# DragonHeadv2.net
KiCad netlist of a schematic drawn in EAGLE
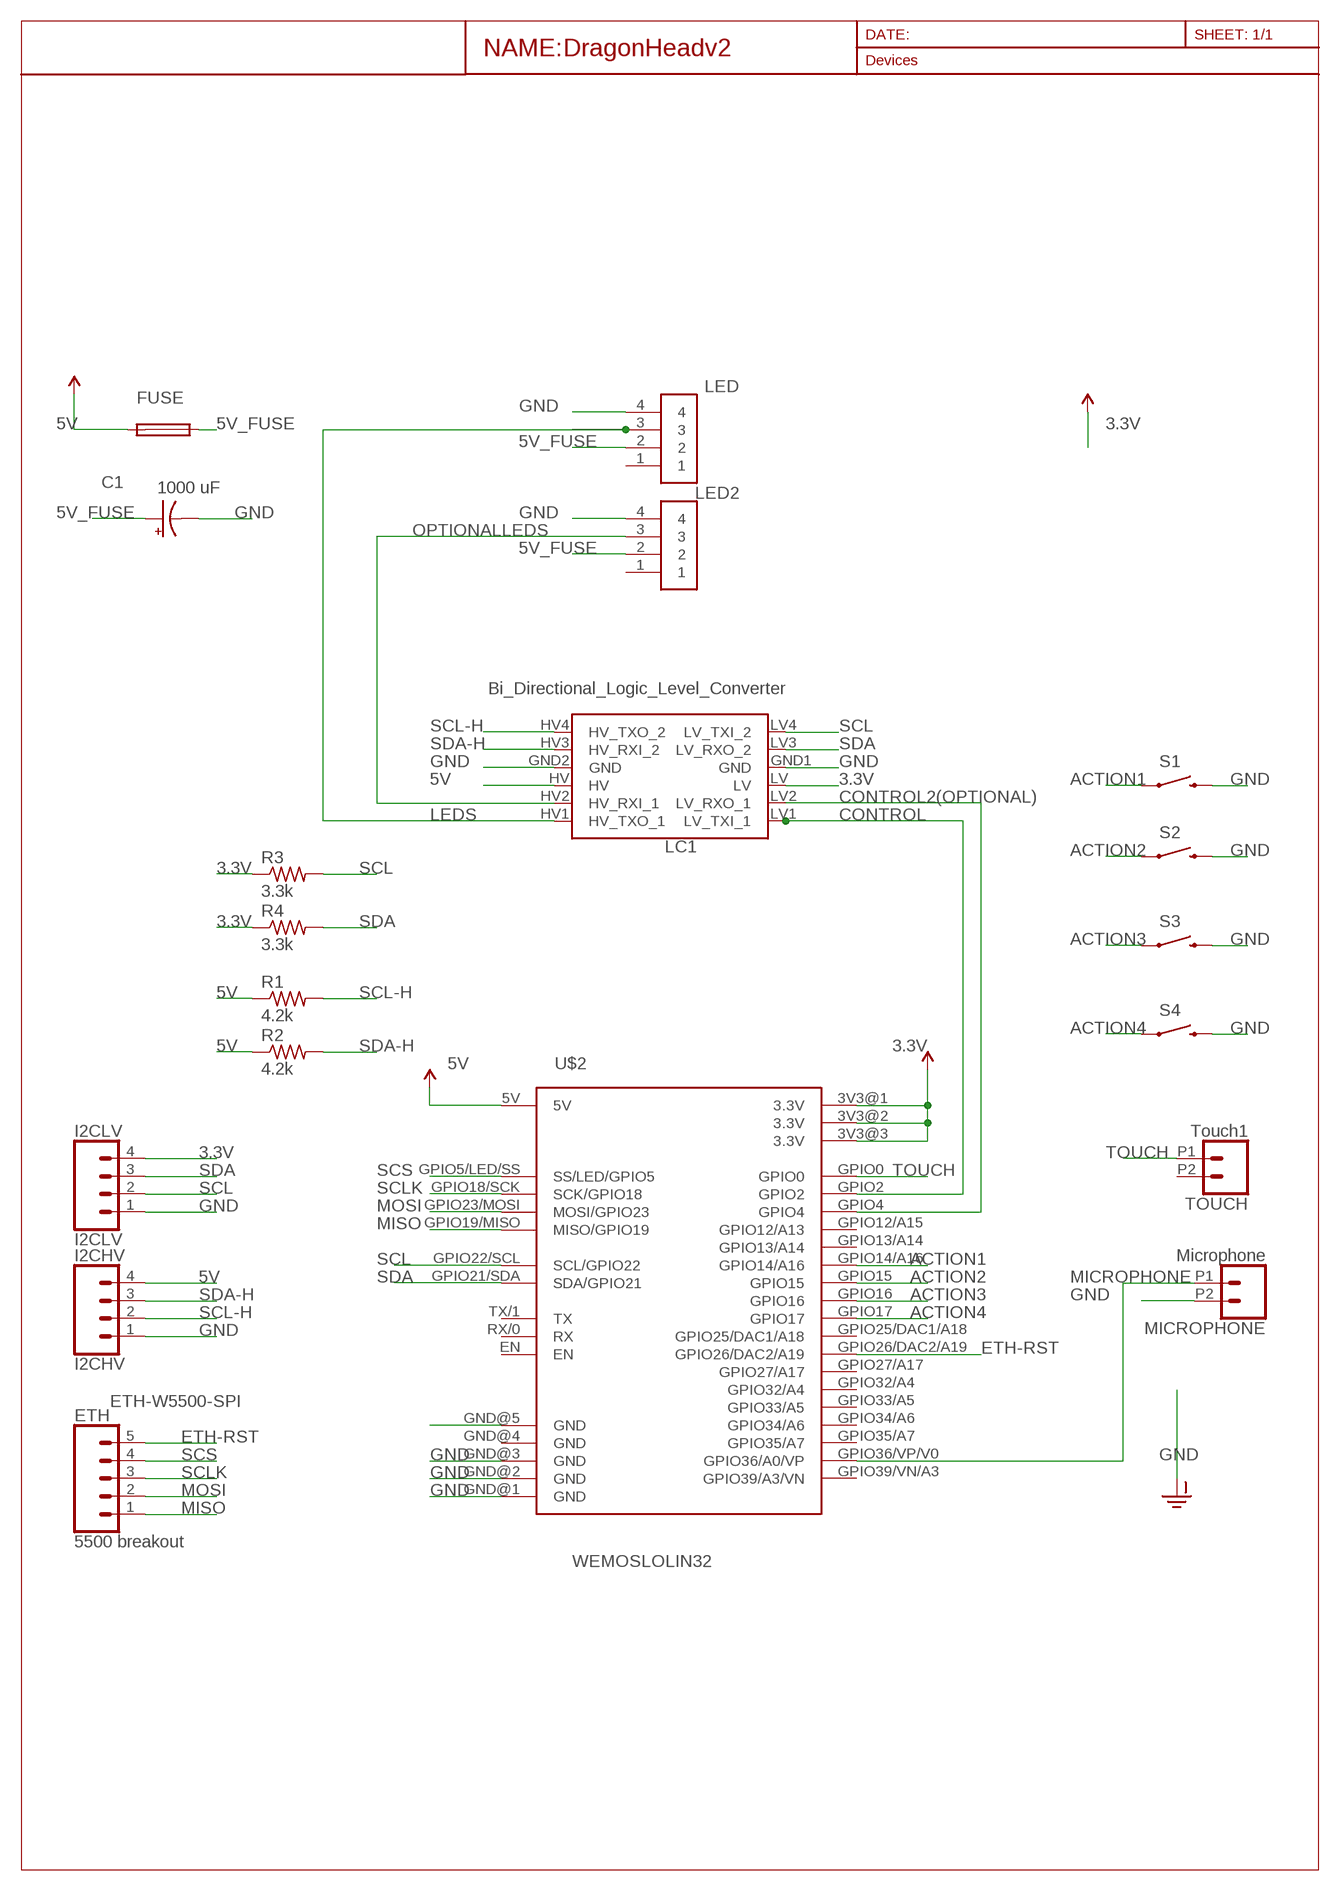
[diagram p0: schematic, sheet 1]

(export (version "E")
  (design (tool "Eeschema 10.0.6"))
  (components
    (comp (ref "C1")
      (value "1000 uF")
      (footprint "eagle-import:CPOL-RADIAL-5MM-10MM")
      (libsource (lib "eagle-import") (part "1000UF-RADIAL-5MM-25V-20%"))
    )
    (comp (ref "ETH")
      (value "5500 breakout")
      (footprint "eagle-import:1X05")
      (libsource (lib "eagle-import") (part "CONN_05"))
    )
    (comp (ref "FUSE")
      (value "FUSEBLANK_5X20MM")
      (footprint "eagle-import:FUSE_HOLDER_5X20MM")
      (libsource (lib "eagle-import") (part "FUSEBLANK_5X20MM"))
    )
    (comp (ref "I2CHV")
      (value "I2CHV")
      (footprint "eagle-import:1X04")
      (libsource (lib "eagle-import") (part "CONN_04PTH"))
    )
    (comp (ref "I2CLV")
      (value "I2CLV")
      (footprint "eagle-import:1X04")
      (libsource (lib "eagle-import") (part "CONN_04PTH"))
    )
    (comp (ref "LC1")
      (value "Bi_Directional_Logic_Level_Converter")
      (footprint "eagle-import:SPARKFUN_LOGIC_LEVEL_CONVERTER")
      (libsource (lib "eagle-import") (part "SPARKFUN_LOGIC_LEVEL_CONVERTER"))
    )
    (comp (ref "LED")
      (value "231-334/001-000")
      (footprint "eagle-import:WAGO_231-334_001-000")
      (fields (field (name "MF") "WAGO"))
      (libsource (lib "eagle-import") (part "231-334/001-000"))
    )
    (comp (ref "LED2")
      (value "231-334/001-000")
      (footprint "eagle-import:WAGO_231-334_001-000")
      (fields (field (name "MF") "WAGO"))
      (libsource (lib "eagle-import") (part "231-334/001-000"))
    )
    (comp (ref "MICROPHONE")
      (value "Microphone")
      (footprint "eagle-import:1X02_2.54_SCREWTERM")
      (libsource (lib "eagle-import") (part "CONN_022.54MM_SCREWTERM"))
    )
    (comp (ref "R1")
      (value "4.2k")
      (footprint "eagle-import:0204_7")
      (libsource (lib "eagle-import") (part "R-US_0204/7"))
    )
    (comp (ref "R2")
      (value "4.2k")
      (footprint "eagle-import:0204_7")
      (libsource (lib "eagle-import") (part "R-US_0204/7"))
    )
    (comp (ref "R3")
      (value "3.3k")
      (footprint "eagle-import:0204_7")
      (libsource (lib "eagle-import") (part "R-US_0204/7"))
    )
    (comp (ref "R4")
      (value "3.3k")
      (footprint "eagle-import:0204_7")
      (libsource (lib "eagle-import") (part "R-US_0204/7"))
    )
    (comp (ref "S1")
      (value "SWITCH-MOMENTARY-2SIDE_EZ")
      (footprint "eagle-import:TACTILE-PTH-SIDEEZ")
      (libsource (lib "eagle-import") (part "SWITCH-MOMENTARY-2SIDE_EZ"))
    )
    (comp (ref "S2")
      (value "SWITCH-MOMENTARY-2SIDE_EZ")
      (footprint "eagle-import:TACTILE-PTH-SIDEEZ")
      (libsource (lib "eagle-import") (part "SWITCH-MOMENTARY-2SIDE_EZ"))
    )
    (comp (ref "S3")
      (value "SWITCH-MOMENTARY-2SIDE_EZ")
      (footprint "eagle-import:TACTILE-PTH-SIDEEZ")
      (libsource (lib "eagle-import") (part "SWITCH-MOMENTARY-2SIDE_EZ"))
    )
    (comp (ref "S4")
      (value "SWITCH-MOMENTARY-2SIDE_EZ")
      (footprint "eagle-import:TACTILE-PTH-SIDEEZ")
      (libsource (lib "eagle-import") (part "SWITCH-MOMENTARY-2SIDE_EZ"))
    )
    (comp (ref "TOUCH")
      (value "Touch1")
      (footprint "eagle-import:1X02_2.54_SCREWTERM")
      (libsource (lib "eagle-import") (part "CONN_022.54MM_SCREWTERM"))
    )
    (comp (ref "U$2")
      (value "WEMOSLOLIN32")
      (footprint "eagle-import:LOLIN32VAR1")
      (libsource (lib "eagle-import") (part "WEMOSLOLIN32"))
    )
  )
  (nets
    (net (code "1") (name "/5V_FUSE") (class "Default")
      (node (ref "C1") (pin "+") (pinfunction "+_+") (pintype "passive"))
      (node (ref "FUSE") (pin "1") (pinfunction "1_1") (pintype "passive"))
      (node (ref "LED") (pin "2") (pinfunction "2_2") (pintype "passive"))
      (node (ref "LED2") (pin "2") (pinfunction "2_2") (pintype "passive"))
    )
    (net (code "2") (name "/ACTION1") (class "Default")
      (node (ref "S1") (pin "1") (pinfunction "1_1") (pintype "passive"))
      (node (ref "U$2") (pin "GPIO14/A16") (pinfunction "GPIO14/A16_GPIO14/A16") (pintype "bidirectional"))
    )
    (net (code "3") (name "/ACTION2") (class "Default")
      (node (ref "S2") (pin "1") (pinfunction "1_1") (pintype "passive"))
      (node (ref "U$2") (pin "GPIO15") (pinfunction "GPIO15_GPIO15") (pintype "bidirectional"))
    )
    (net (code "4") (name "/ACTION3") (class "Default")
      (node (ref "S3") (pin "1") (pinfunction "1_1") (pintype "passive"))
      (node (ref "U$2") (pin "GPIO16") (pinfunction "GPIO16_GPIO16") (pintype "bidirectional"))
    )
    (net (code "5") (name "/ACTION4") (class "Default")
      (node (ref "S4") (pin "1") (pinfunction "1_1") (pintype "passive"))
      (node (ref "U$2") (pin "GPIO17") (pinfunction "GPIO17_GPIO17") (pintype "bidirectional"))
    )
    (net (code "6") (name "/CONTROL") (class "Default")
      (node (ref "LC1") (pin "LV1") (pinfunction "LV_TXI_1_LV1") (pintype "bidirectional"))
      (node (ref "U$2") (pin "GPIO2") (pinfunction "GPIO2_GPIO2") (pintype "bidirectional"))
    )
    (net (code "7") (name "/CONTROL2(OPTIONAL)") (class "Default")
      (node (ref "LC1") (pin "LV2") (pinfunction "LV_RXO_1_LV2") (pintype "bidirectional"))
      (node (ref "U$2") (pin "GPIO4") (pinfunction "GPIO4_GPIO4") (pintype "bidirectional"))
    )
    (net (code "8") (name "/ETH-RST") (class "Default")
      (node (ref "ETH") (pin "5") (pinfunction "5_5") (pintype "passive"))
      (node (ref "U$2") (pin "GPIO26/DAC2/A19") (pinfunction "GPIO26/DAC2/A19_GPIO26/DAC2/A19") (pintype "bidirectional"))
    )
    (net (code "9") (name "/LEDS") (class "Default")
      (node (ref "LC1") (pin "HV1") (pinfunction "HV_TXO_1_HV1") (pintype "bidirectional"))
      (node (ref "LED") (pin "3") (pinfunction "3_3") (pintype "passive"))
    )
    (net (code "10") (name "/MICROPHONE") (class "Default")
      (node (ref "MICROPHONE") (pin "P1") (pinfunction "1_P1") (pintype "passive"))
      (node (ref "U$2") (pin "GPIO36/VP/V0") (pinfunction "GPIO36/A0/VP_GPIO36/VP/V0") (pintype "bidirectional"))
    )
    (net (code "11") (name "/MISO") (class "Default")
      (node (ref "ETH") (pin "1") (pinfunction "1_1") (pintype "passive"))
      (node (ref "U$2") (pin "GPIO19/MISO") (pinfunction "MISO/GPIO19_GPIO19/MISO") (pintype "bidirectional"))
    )
    (net (code "12") (name "/MOSI") (class "Default")
      (node (ref "ETH") (pin "2") (pinfunction "2_2") (pintype "passive"))
      (node (ref "U$2") (pin "GPIO23/MOSI") (pinfunction "MOSI/GPIO23_GPIO23/MOSI") (pintype "bidirectional"))
    )
    (net (code "13") (name "/OPTIONALLEDS") (class "Default")
      (node (ref "LC1") (pin "HV2") (pinfunction "HV_RXI_1_HV2") (pintype "bidirectional"))
      (node (ref "LED2") (pin "3") (pinfunction "3_3") (pintype "passive"))
    )
    (net (code "14") (name "/SCL") (class "Default")
      (node (ref "I2CLV") (pin "2") (pinfunction "2_2") (pintype "passive"))
      (node (ref "LC1") (pin "LV4") (pinfunction "LV_TXI_2_LV4") (pintype "bidirectional"))
      (node (ref "R3") (pin "2") (pinfunction "2_2") (pintype "passive"))
      (node (ref "U$2") (pin "GPIO22/SCL") (pinfunction "SCL/GPIO22_GPIO22/SCL") (pintype "bidirectional"))
    )
    (net (code "15") (name "/SCL-H") (class "Default")
      (node (ref "I2CHV") (pin "2") (pinfunction "2_2") (pintype "passive"))
      (node (ref "LC1") (pin "HV4") (pinfunction "HV_TXO_2_HV4") (pintype "bidirectional"))
      (node (ref "R1") (pin "2") (pinfunction "2_2") (pintype "passive"))
    )
    (net (code "16") (name "/SCLK") (class "Default")
      (node (ref "ETH") (pin "3") (pinfunction "3_3") (pintype "passive"))
      (node (ref "U$2") (pin "GPIO18/SCK") (pinfunction "SCK/GPIO18_GPIO18/SCK") (pintype "bidirectional"))
    )
    (net (code "17") (name "/SCS") (class "Default")
      (node (ref "ETH") (pin "4") (pinfunction "4_4") (pintype "passive"))
      (node (ref "U$2") (pin "GPIO5/LED/SS") (pinfunction "SS/LED/GPIO5_GPIO5/LED/SS") (pintype "bidirectional"))
    )
    (net (code "18") (name "/SDA") (class "Default")
      (node (ref "I2CLV") (pin "3") (pinfunction "3_3") (pintype "passive"))
      (node (ref "LC1") (pin "LV3") (pinfunction "LV_RXO_2_LV3") (pintype "bidirectional"))
      (node (ref "R4") (pin "2") (pinfunction "2_2") (pintype "passive"))
      (node (ref "U$2") (pin "GPIO21/SDA") (pinfunction "SDA/GPIO21_GPIO21/SDA") (pintype "bidirectional"))
    )
    (net (code "19") (name "/SDA-H") (class "Default")
      (node (ref "I2CHV") (pin "3") (pinfunction "3_3") (pintype "passive"))
      (node (ref "LC1") (pin "HV3") (pinfunction "HV_RXI_2_HV3") (pintype "bidirectional"))
      (node (ref "R2") (pin "2") (pinfunction "2_2") (pintype "passive"))
    )
    (net (code "20") (name "/TOUCH") (class "Default")
      (node (ref "TOUCH") (pin "P1") (pinfunction "1_P1") (pintype "passive"))
      (node (ref "U$2") (pin "GPIO0") (pinfunction "GPIO0_GPIO0") (pintype "bidirectional"))
    )
    (net (code "21") (name "3.3V") (class "Default")
      (node (ref "I2CLV") (pin "4") (pinfunction "4_4") (pintype "passive"))
      (node (ref "LC1") (pin "LV") (pinfunction "LV_LV") (pintype "power_in"))
      (node (ref "R3") (pin "1") (pinfunction "1_1") (pintype "passive"))
      (node (ref "R4") (pin "1") (pinfunction "1_1") (pintype "passive"))
      (node (ref "U$2") (pin "3V3@1") (pinfunction "3.3V_3V3@1") (pintype "bidirectional"))
      (node (ref "U$2") (pin "3V3@2") (pinfunction "3.3V_3V3@2") (pintype "bidirectional"))
      (node (ref "U$2") (pin "3V3@3") (pinfunction "3.3V_3V3@3") (pintype "power_in"))
    )
    (net (code "22") (name "5V") (class "Default")
      (node (ref "FUSE") (pin "2") (pinfunction "2_2") (pintype "passive"))
      (node (ref "I2CHV") (pin "4") (pinfunction "4_4") (pintype "passive"))
      (node (ref "LC1") (pin "HV") (pinfunction "HV_HV") (pintype "power_in"))
      (node (ref "R1") (pin "1") (pinfunction "1_1") (pintype "passive"))
      (node (ref "R2") (pin "1") (pinfunction "1_1") (pintype "passive"))
      (node (ref "U$2") (pin "5V") (pinfunction "5V_5V") (pintype "power_in"))
    )
    (net (code "23") (name "GND-ISO") (class "Default")
      (node (ref "C1") (pin "-") (pinfunction "-_-") (pintype "passive"))
      (node (ref "I2CHV") (pin "1") (pinfunction "1_1") (pintype "passive"))
      (node (ref "I2CLV") (pin "1") (pinfunction "1_1") (pintype "passive"))
      (node (ref "LC1") (pin "GND1") (pinfunction "GND_GND1") (pintype "power_in"))
      (node (ref "LC1") (pin "GND2") (pinfunction "GND_GND2") (pintype "power_in"))
      (node (ref "LED") (pin "4") (pinfunction "4_4") (pintype "passive"))
      (node (ref "LED2") (pin "4") (pinfunction "4_4") (pintype "passive"))
      (node (ref "MICROPHONE") (pin "P2") (pinfunction "2_P2") (pintype "passive"))
      (node (ref "S1") (pin "2") (pinfunction "2_2") (pintype "passive"))
      (node (ref "S2") (pin "2") (pinfunction "2_2") (pintype "passive"))
      (node (ref "S3") (pin "2") (pinfunction "2_2") (pintype "passive"))
      (node (ref "S4") (pin "2") (pinfunction "2_2") (pintype "passive"))
      (node (ref "U$2") (pin "GND@1") (pinfunction "GND_GND@1") (pintype "power_in"))
      (node (ref "U$2") (pin "GND@2") (pinfunction "GND_GND@2") (pintype "bidirectional"))
      (node (ref "U$2") (pin "GND@3") (pinfunction "GND_GND@3") (pintype "bidirectional"))
      (node (ref "U$2") (pin "GND@5") (pinfunction "GND_GND@5") (pintype "bidirectional"))
    )
    (net (code "24") (name "unconnected-(LED-Pad1)") (class "Default")
      (node (ref "LED") (pin "1") (pinfunction "1_1") (pintype "passive"))
    )
    (net (code "25") (name "unconnected-(LED2-Pad1)") (class "Default")
      (node (ref "LED2") (pin "1") (pinfunction "1_1") (pintype "passive"))
    )
    (net (code "26") (name "unconnected-(TOUCH-2-PadP2)") (class "Default")
      (node (ref "TOUCH") (pin "P2") (pinfunction "2_P2") (pintype "passive"))
    )
    (net (code "27") (name "unconnected-(U$2-GND-PadGND@4)") (class "Default")
      (node (ref "U$2") (pin "GND@4") (pinfunction "GND_GND@4") (pintype "bidirectional"))
    )
    (net (code "28") (name "unconnected-(U$2-GPIO12{slash}A13-PadGPIO12{slash}A15)") (class "Default")
      (node (ref "U$2") (pin "GPIO12/A15") (pinfunction "GPIO12/A13_GPIO12/A15") (pintype "bidirectional"))
    )
    (net (code "29") (name "unconnected-(U$2-GPIO39{slash}A3{slash}VN-PadGPIO39{slash}VN{slash}A3)") (class "Default")
      (node (ref "U$2") (pin "GPIO39/VN/A3") (pinfunction "GPIO39/A3/VN_GPIO39/VN/A3") (pintype "bidirectional"))
    )
    (net (code "30") (name "unconnected-(U$2-PadEN)") (class "Default")
      (node (ref "U$2") (pin "EN") (pinfunction "EN_EN") (pintype "bidirectional"))
    )
    (net (code "31") (name "unconnected-(U$2-PadGPIO13{slash}A14)") (class "Default")
      (node (ref "U$2") (pin "GPIO13/A14") (pinfunction "GPIO13/A14_GPIO13/A14") (pintype "bidirectional"))
    )
    (net (code "32") (name "unconnected-(U$2-PadGPIO25{slash}DAC1{slash}A18)") (class "Default")
      (node (ref "U$2") (pin "GPIO25/DAC1/A18") (pinfunction "GPIO25/DAC1/A18_GPIO25/DAC1/A18") (pintype "bidirectional"))
    )
    (net (code "33") (name "unconnected-(U$2-PadGPIO27{slash}A17)") (class "Default")
      (node (ref "U$2") (pin "GPIO27/A17") (pinfunction "GPIO27/A17_GPIO27/A17") (pintype "bidirectional"))
    )
    (net (code "34") (name "unconnected-(U$2-PadGPIO32{slash}A4)") (class "Default")
      (node (ref "U$2") (pin "GPIO32/A4") (pinfunction "GPIO32/A4_GPIO32/A4") (pintype "bidirectional"))
    )
    (net (code "35") (name "unconnected-(U$2-PadGPIO33{slash}A5)") (class "Default")
      (node (ref "U$2") (pin "GPIO33/A5") (pinfunction "GPIO33/A5_GPIO33/A5") (pintype "bidirectional"))
    )
    (net (code "36") (name "unconnected-(U$2-PadGPIO34{slash}A6)") (class "Default")
      (node (ref "U$2") (pin "GPIO34/A6") (pinfunction "GPIO34/A6_GPIO34/A6") (pintype "bidirectional"))
    )
    (net (code "37") (name "unconnected-(U$2-PadGPIO35{slash}A7)") (class "Default")
      (node (ref "U$2") (pin "GPIO35/A7") (pinfunction "GPIO35/A7_GPIO35/A7") (pintype "bidirectional"))
    )
    (net (code "38") (name "unconnected-(U$2-RX-PadRX{slash}0)") (class "Default")
      (node (ref "U$2") (pin "RX/0") (pinfunction "RX_RX/0") (pintype "input"))
    )
    (net (code "39") (name "unconnected-(U$2-TX-PadTX{slash}1)") (class "Default")
      (node (ref "U$2") (pin "TX/1") (pinfunction "TX_TX/1") (pintype "output"))
    )
  )
)
